# remote.net
KiCad netlist of a schematic drawn in EAGLE
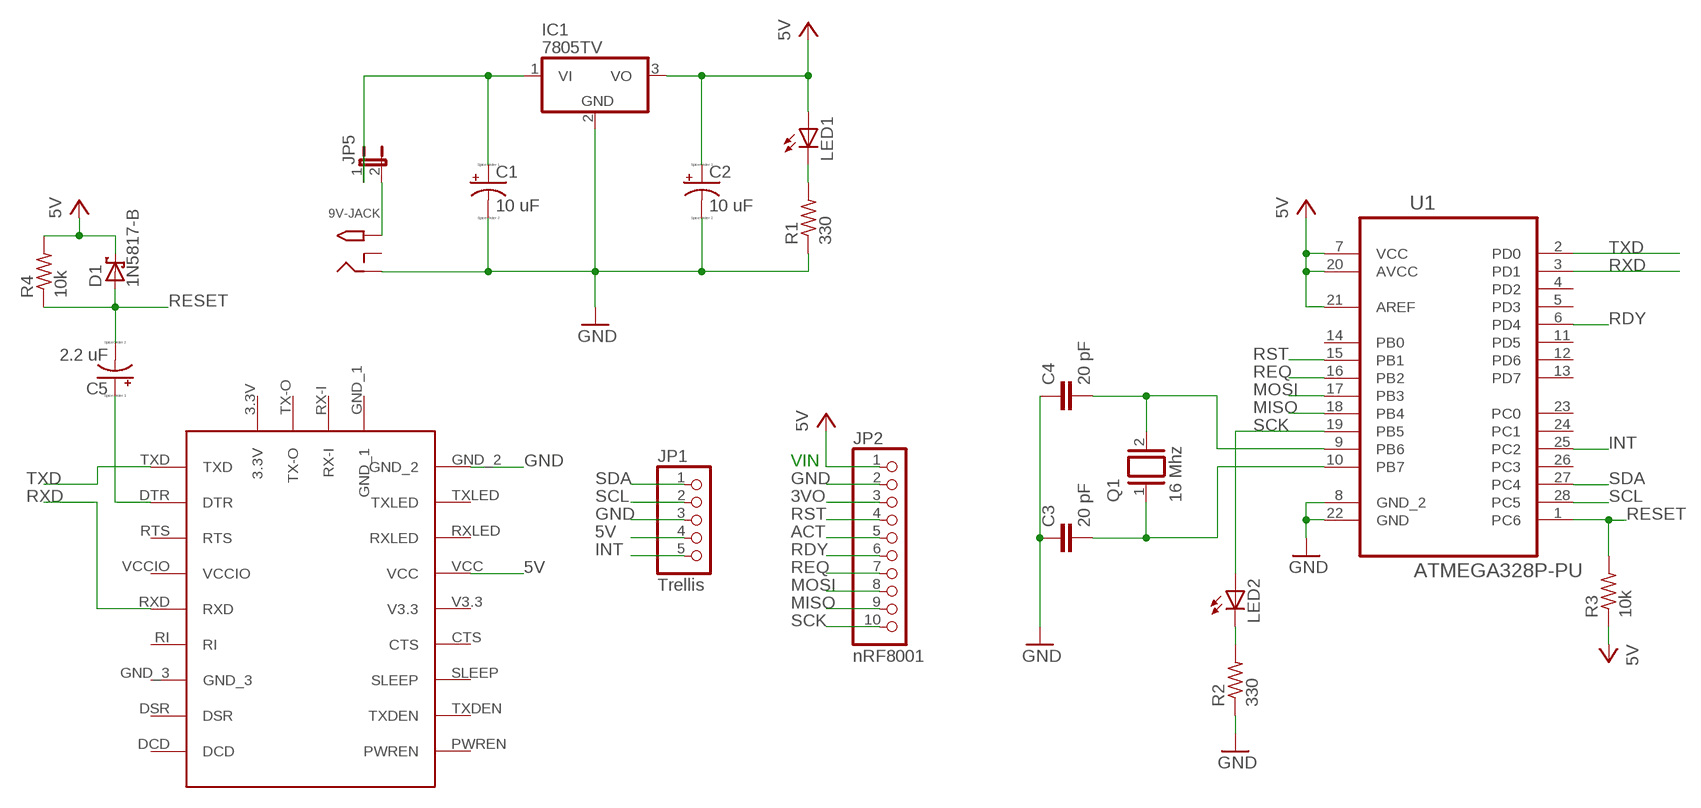
[diagram p0: schematic, sheet 1]

(export (version "E")
  (design (tool "Eeschema 10.0.6"))
  (components
    (comp (ref "9V-JACK")
      (value "9V Input")
      (footprint "eagle-import:PJ-102A")
      (libsource (lib "eagle-import") (part "2.1MMJACKTHM"))
    )
    (comp (ref "C1")
      (value "10 uF")
      (footprint "eagle-import:B45181B")
      (libsource (lib "eagle-import") (part "CPOL-USB45181B"))
    )
    (comp (ref "C2")
      (value "10 uF")
      (footprint "eagle-import:B45181B")
      (libsource (lib "eagle-import") (part "CPOL-USB45181B"))
    )
    (comp (ref "C3")
      (value "20 pF")
      (footprint "eagle-import:C050-025X075")
      (libsource (lib "eagle-import") (part "C-EU050-025X075"))
    )
    (comp (ref "C4")
      (value "20 pF")
      (footprint "eagle-import:C050-025X075")
      (libsource (lib "eagle-import") (part "C-EU050-025X075"))
    )
    (comp (ref "C5")
      (value "2.2 uF")
      (footprint "eagle-import:B45181B")
      (libsource (lib "eagle-import") (part "CPOL-USB45181B"))
    )
    (comp (ref "D1")
      (value "1N5817-B")
      (footprint "eagle-import:DO41-7.6")
      (libsource (lib "eagle-import") (part "1N5817-B"))
    )
    (comp (ref "IC1")
      (value "7805TV")
      (footprint "eagle-import:TO220V")
      (libsource (lib "eagle-import") (part "78TV05"))
    )
    (comp (ref "JP1")
      (value "Trellis")
      (footprint "eagle-import:1X05")
      (libsource (lib "eagle-import") (part "PINHD-1X5"))
    )
    (comp (ref "JP2")
      (value "nRF8001")
      (footprint "eagle-import:1X10")
      (libsource (lib "eagle-import") (part "PINHD-1X10"))
    )
    (comp (ref "JP5")
      (value "JP1E")
      (footprint "eagle-import:JP1")
      (libsource (lib "eagle-import") (part "JP1E"))
    )
    (comp (ref "LED1")
      (value "LED3MM")
      (footprint "eagle-import:LED3MM")
      (libsource (lib "eagle-import") (part "LED3MM"))
    )
    (comp (ref "LED2")
      (value "LED3MM")
      (footprint "eagle-import:LED3MM")
      (libsource (lib "eagle-import") (part "LED3MM"))
    )
    (comp (ref "Q1")
      (value "16 Mhz")
      (footprint "eagle-import:QS")
      (libsource (lib "eagle-import") (part "XTAL/S"))
    )
    (comp (ref "R1")
      (value "330")
      (footprint "eagle-import:RES400MIL")
      (libsource (lib "eagle-import") (part "RESISTOR0309/10"))
    )
    (comp (ref "R2")
      (value "330")
      (footprint "eagle-import:RES400MIL")
      (libsource (lib "eagle-import") (part "RESISTOR0309/10"))
    )
    (comp (ref "R3")
      (value "10k")
      (footprint "eagle-import:RES400MIL")
      (libsource (lib "eagle-import") (part "RESISTOR0309/10"))
    )
    (comp (ref "R4")
      (value "10k")
      (footprint "eagle-import:RES400MIL")
      (libsource (lib "eagle-import") (part "RESISTOR0309/10"))
    )
    (comp (ref "U$1")
      (value "FT232")
      (footprint "eagle-import:FT232")
      (libsource (lib "eagle-import") (part "FT232"))
    )
    (comp (ref "U1")
      (value "ATMEGA328P-PU")
      (footprint "eagle-import:DIP254P762X457-28")
      (libsource (lib "eagle-import") (part "ATMEGA328P-PU"))
    )
  )
  (nets
    (net (code "1") (name "/3VO") (class "Default")
      (node (ref "JP2") (pin "3") (pinfunction "3_3") (pintype "passive"))
    )
    (net (code "2") (name "/ACT") (class "Default")
      (node (ref "JP2") (pin "5") (pinfunction "5_5") (pintype "passive"))
    )
    (net (code "3") (name "/INT") (class "Default")
      (node (ref "JP1") (pin "5") (pinfunction "5_5") (pintype "passive"))
      (node (ref "U1") (pin "25") (pinfunction "PC2_25") (pintype "bidirectional"))
    )
    (net (code "4") (name "/MISO") (class "Default")
      (node (ref "JP2") (pin "9") (pinfunction "9_9") (pintype "passive"))
      (node (ref "U1") (pin "18") (pinfunction "PB4_18") (pintype "bidirectional"))
    )
    (net (code "5") (name "/MOSI") (class "Default")
      (node (ref "JP2") (pin "8") (pinfunction "8_8") (pintype "passive"))
      (node (ref "U1") (pin "17") (pinfunction "PB3_17") (pintype "bidirectional"))
    )
    (net (code "6") (name "/RDY") (class "Default")
      (node (ref "JP2") (pin "6") (pinfunction "6_6") (pintype "passive"))
      (node (ref "U1") (pin "6") (pinfunction "PD4_6") (pintype "bidirectional"))
    )
    (net (code "7") (name "/REQ") (class "Default")
      (node (ref "JP2") (pin "7") (pinfunction "7_7") (pintype "passive"))
      (node (ref "U1") (pin "16") (pinfunction "PB2_16") (pintype "bidirectional"))
    )
    (net (code "8") (name "/RESET") (class "Default")
      (node (ref "C5") (pin "-") (pinfunction "-_-") (pintype "passive"))
      (node (ref "D1") (pin "A") (pinfunction "A_A") (pintype "passive"))
      (node (ref "R3") (pin "2") (pinfunction "2_2") (pintype "passive"))
      (node (ref "R4") (pin "1") (pinfunction "1_1") (pintype "passive"))
      (node (ref "U1") (pin "1") (pinfunction "PC6_1") (pintype "bidirectional"))
    )
    (net (code "9") (name "/RST") (class "Default")
      (node (ref "JP2") (pin "4") (pinfunction "4_4") (pintype "passive"))
      (node (ref "U1") (pin "15") (pinfunction "PB1_15") (pintype "bidirectional"))
    )
    (net (code "10") (name "/RXD") (class "Default")
      (node (ref "U$1") (pin "RXD") (pinfunction "RXD_RXD") (pintype "bidirectional"))
      (node (ref "U1") (pin "3") (pinfunction "PD1_3") (pintype "bidirectional"))
    )
    (net (code "11") (name "/SCK") (class "Default")
      (node (ref "JP2") (pin "10") (pinfunction "10_10") (pintype "passive"))
      (node (ref "LED2") (pin "A") (pinfunction "A_A") (pintype "passive"))
      (node (ref "U1") (pin "19") (pinfunction "PB5_19") (pintype "bidirectional"))
    )
    (net (code "12") (name "/SCL") (class "Default")
      (node (ref "JP1") (pin "2") (pinfunction "2_2") (pintype "passive"))
      (node (ref "U1") (pin "28") (pinfunction "PC5_28") (pintype "bidirectional"))
    )
    (net (code "13") (name "/SDA") (class "Default")
      (node (ref "JP1") (pin "1") (pinfunction "1_1") (pintype "passive"))
      (node (ref "U1") (pin "27") (pinfunction "PC4_27") (pintype "bidirectional"))
    )
    (net (code "14") (name "/TXD") (class "Default")
      (node (ref "U$1") (pin "TXD") (pinfunction "TXD_TXD") (pintype "bidirectional"))
      (node (ref "U1") (pin "2") (pinfunction "PD0_2") (pintype "bidirectional"))
    )
    (net (code "15") (name "5V") (class "Default")
      (node (ref "C2") (pin "+") (pinfunction "+_+") (pintype "passive"))
      (node (ref "D1") (pin "C") (pinfunction "C_C") (pintype "passive"))
      (node (ref "IC1") (pin "3") (pinfunction "VO_3") (pintype "passive"))
      (node (ref "JP1") (pin "4") (pinfunction "4_4") (pintype "passive"))
      (node (ref "JP2") (pin "1") (pinfunction "1_1") (pintype "passive"))
      (node (ref "LED1") (pin "A") (pinfunction "A_A") (pintype "passive"))
      (node (ref "R3") (pin "1") (pinfunction "1_1") (pintype "passive"))
      (node (ref "R4") (pin "2") (pinfunction "2_2") (pintype "passive"))
      (node (ref "U$1") (pin "VCC") (pinfunction "VCC_VCC") (pintype "bidirectional"))
      (node (ref "U1") (pin "20") (pinfunction "AVCC_20") (pintype "power_in"))
      (node (ref "U1") (pin "21") (pinfunction "AREF_21") (pintype "input"))
      (node (ref "U1") (pin "7") (pinfunction "VCC_7") (pintype "power_in"))
    )
    (net (code "16") (name "GND") (class "Default")
      (node (ref "9V-JACK") (pin "RING") (pinfunction "RING_RING") (pintype "bidirectional"))
      (node (ref "C1") (pin "-") (pinfunction "-_-") (pintype "passive"))
      (node (ref "C2") (pin "-") (pinfunction "-_-") (pintype "passive"))
      (node (ref "C3") (pin "1") (pinfunction "1_1") (pintype "passive"))
      (node (ref "C4") (pin "1") (pinfunction "1_1") (pintype "passive"))
      (node (ref "IC1") (pin "2") (pinfunction "GND_2") (pintype "passive"))
      (node (ref "JP1") (pin "3") (pinfunction "3_3") (pintype "passive"))
      (node (ref "JP2") (pin "2") (pinfunction "2_2") (pintype "passive"))
      (node (ref "R1") (pin "1") (pinfunction "1_1") (pintype "passive"))
      (node (ref "R2") (pin "1") (pinfunction "1_1") (pintype "passive"))
      (node (ref "U$1") (pin "GND_2") (pinfunction "GND_2_GND_2") (pintype "bidirectional"))
      (node (ref "U1") (pin "22") (pinfunction "GND_22") (pintype "passive"))
      (node (ref "U1") (pin "8") (pinfunction "GND_2_8") (pintype "passive"))
    )
    (net (code "17") (name "Net-(9V-JACK-PadTIP)") (class "Default")
      (node (ref "9V-JACK") (pin "TIP") (pinfunction "TIP_TIP") (pintype "bidirectional"))
      (node (ref "JP5") (pin "2") (pinfunction "2_2") (pintype "passive"))
    )
    (net (code "18") (name "Net-(C5-Pad+)") (class "Default")
      (node (ref "C5") (pin "+") (pinfunction "+_+") (pintype "passive"))
      (node (ref "U$1") (pin "DTR") (pinfunction "DTR_DTR") (pintype "bidirectional"))
    )
    (net (code "19") (name "Net-(IC1-VI)") (class "Default")
      (node (ref "C1") (pin "+") (pinfunction "+_+") (pintype "passive"))
      (node (ref "IC1") (pin "1") (pinfunction "VI_1") (pintype "input"))
      (node (ref "JP5") (pin "1") (pinfunction "1_1") (pintype "passive"))
    )
    (net (code "20") (name "Net-(LED1-C)") (class "Default")
      (node (ref "LED1") (pin "K") (pinfunction "C_K") (pintype "passive"))
      (node (ref "R1") (pin "2") (pinfunction "2_2") (pintype "passive"))
    )
    (net (code "21") (name "Net-(LED2-C)") (class "Default")
      (node (ref "LED2") (pin "K") (pinfunction "C_K") (pintype "passive"))
      (node (ref "R2") (pin "2") (pinfunction "2_2") (pintype "passive"))
    )
    (net (code "22") (name "Net-(U1-PB6)") (class "Default")
      (node (ref "C4") (pin "2") (pinfunction "2_2") (pintype "passive"))
      (node (ref "Q1") (pin "2") (pinfunction "2_2") (pintype "passive"))
      (node (ref "U1") (pin "9") (pinfunction "PB6_9") (pintype "bidirectional"))
    )
    (net (code "23") (name "Net-(U1-PB7)") (class "Default")
      (node (ref "C3") (pin "2") (pinfunction "2_2") (pintype "passive"))
      (node (ref "Q1") (pin "1") (pinfunction "1_1") (pintype "passive"))
      (node (ref "U1") (pin "10") (pinfunction "PB7_10") (pintype "bidirectional"))
    )
    (net (code "24") (name "unconnected-(9V-JACK-PadRING_SW)") (class "Default")
      (node (ref "9V-JACK") (pin "RING_SW") (pinfunction "RING_SW_RING_SW") (pintype "bidirectional"))
    )
    (net (code "25") (name "unconnected-(U$1-Pad3.3V)") (class "Default")
      (node (ref "U$1") (pin "3.3V") (pinfunction "3.3V_3.3V") (pintype "bidirectional"))
    )
    (net (code "26") (name "unconnected-(U$1-PadCTS)") (class "Default")
      (node (ref "U$1") (pin "CTS") (pinfunction "CTS_CTS") (pintype "bidirectional"))
    )
    (net (code "27") (name "unconnected-(U$1-PadDCD)") (class "Default")
      (node (ref "U$1") (pin "DCD") (pinfunction "DCD_DCD") (pintype "bidirectional"))
    )
    (net (code "28") (name "unconnected-(U$1-PadDSR)") (class "Default")
      (node (ref "U$1") (pin "DSR") (pinfunction "DSR_DSR") (pintype "bidirectional"))
    )
    (net (code "29") (name "unconnected-(U$1-PadGND_1)") (class "Default")
      (node (ref "U$1") (pin "GND_1") (pinfunction "GND_1_GND_1") (pintype "bidirectional"))
    )
    (net (code "30") (name "unconnected-(U$1-PadGND_3)") (class "Default")
      (node (ref "U$1") (pin "GND_3") (pinfunction "GND_3_GND_3") (pintype "bidirectional"))
    )
    (net (code "31") (name "unconnected-(U$1-PadPWREN)") (class "Default")
      (node (ref "U$1") (pin "PWREN") (pinfunction "PWREN_PWREN") (pintype "bidirectional"))
    )
    (net (code "32") (name "unconnected-(U$1-PadRI)") (class "Default")
      (node (ref "U$1") (pin "RI") (pinfunction "RI_RI") (pintype "bidirectional"))
    )
    (net (code "33") (name "unconnected-(U$1-PadRTS)") (class "Default")
      (node (ref "U$1") (pin "RTS") (pinfunction "RTS_RTS") (pintype "bidirectional"))
    )
    (net (code "34") (name "unconnected-(U$1-PadRX-I)") (class "Default")
      (node (ref "U$1") (pin "RX-I") (pinfunction "RX-I_RX-I") (pintype "bidirectional"))
    )
    (net (code "35") (name "unconnected-(U$1-PadRXLED)") (class "Default")
      (node (ref "U$1") (pin "RXLED") (pinfunction "RXLED_RXLED") (pintype "bidirectional"))
    )
    (net (code "36") (name "unconnected-(U$1-PadSLEEP)") (class "Default")
      (node (ref "U$1") (pin "SLEEP") (pinfunction "SLEEP_SLEEP") (pintype "bidirectional"))
    )
    (net (code "37") (name "unconnected-(U$1-PadTX-O)") (class "Default")
      (node (ref "U$1") (pin "TX-O") (pinfunction "TX-O_TX-O") (pintype "bidirectional"))
    )
    (net (code "38") (name "unconnected-(U$1-PadTXDEN)") (class "Default")
      (node (ref "U$1") (pin "TXDEN") (pinfunction "TXDEN_TXDEN") (pintype "bidirectional"))
    )
    (net (code "39") (name "unconnected-(U$1-PadTXLED)") (class "Default")
      (node (ref "U$1") (pin "TXLED") (pinfunction "TXLED_TXLED") (pintype "bidirectional"))
    )
    (net (code "40") (name "unconnected-(U$1-PadV3.3)") (class "Default")
      (node (ref "U$1") (pin "V3.3") (pinfunction "V3.3_V3.3") (pintype "bidirectional"))
    )
    (net (code "41") (name "unconnected-(U$1-PadVCCIO)") (class "Default")
      (node (ref "U$1") (pin "VCCIO") (pinfunction "VCCIO_VCCIO") (pintype "bidirectional"))
    )
    (net (code "42") (name "unconnected-(U1-PB0-Pad14)") (class "Default")
      (node (ref "U1") (pin "14") (pinfunction "PB0_14") (pintype "bidirectional"))
    )
    (net (code "43") (name "unconnected-(U1-PC0-Pad23)") (class "Default")
      (node (ref "U1") (pin "23") (pinfunction "PC0_23") (pintype "bidirectional"))
    )
    (net (code "44") (name "unconnected-(U1-PC1-Pad24)") (class "Default")
      (node (ref "U1") (pin "24") (pinfunction "PC1_24") (pintype "bidirectional"))
    )
    (net (code "45") (name "unconnected-(U1-PC3-Pad26)") (class "Default")
      (node (ref "U1") (pin "26") (pinfunction "PC3_26") (pintype "bidirectional"))
    )
    (net (code "46") (name "unconnected-(U1-PD2-Pad4)") (class "Default")
      (node (ref "U1") (pin "4") (pinfunction "PD2_4") (pintype "bidirectional"))
    )
    (net (code "47") (name "unconnected-(U1-PD3-Pad5)") (class "Default")
      (node (ref "U1") (pin "5") (pinfunction "PD3_5") (pintype "bidirectional"))
    )
    (net (code "48") (name "unconnected-(U1-PD5-Pad11)") (class "Default")
      (node (ref "U1") (pin "11") (pinfunction "PD5_11") (pintype "bidirectional"))
    )
    (net (code "49") (name "unconnected-(U1-PD6-Pad12)") (class "Default")
      (node (ref "U1") (pin "12") (pinfunction "PD6_12") (pintype "bidirectional"))
    )
    (net (code "50") (name "unconnected-(U1-PD7-Pad13)") (class "Default")
      (node (ref "U1") (pin "13") (pinfunction "PD7_13") (pintype "bidirectional"))
    )
  )
)
